# 6_shkb_upstream_con.net
KiCad netlist of a schematic drawn in Altium Designer
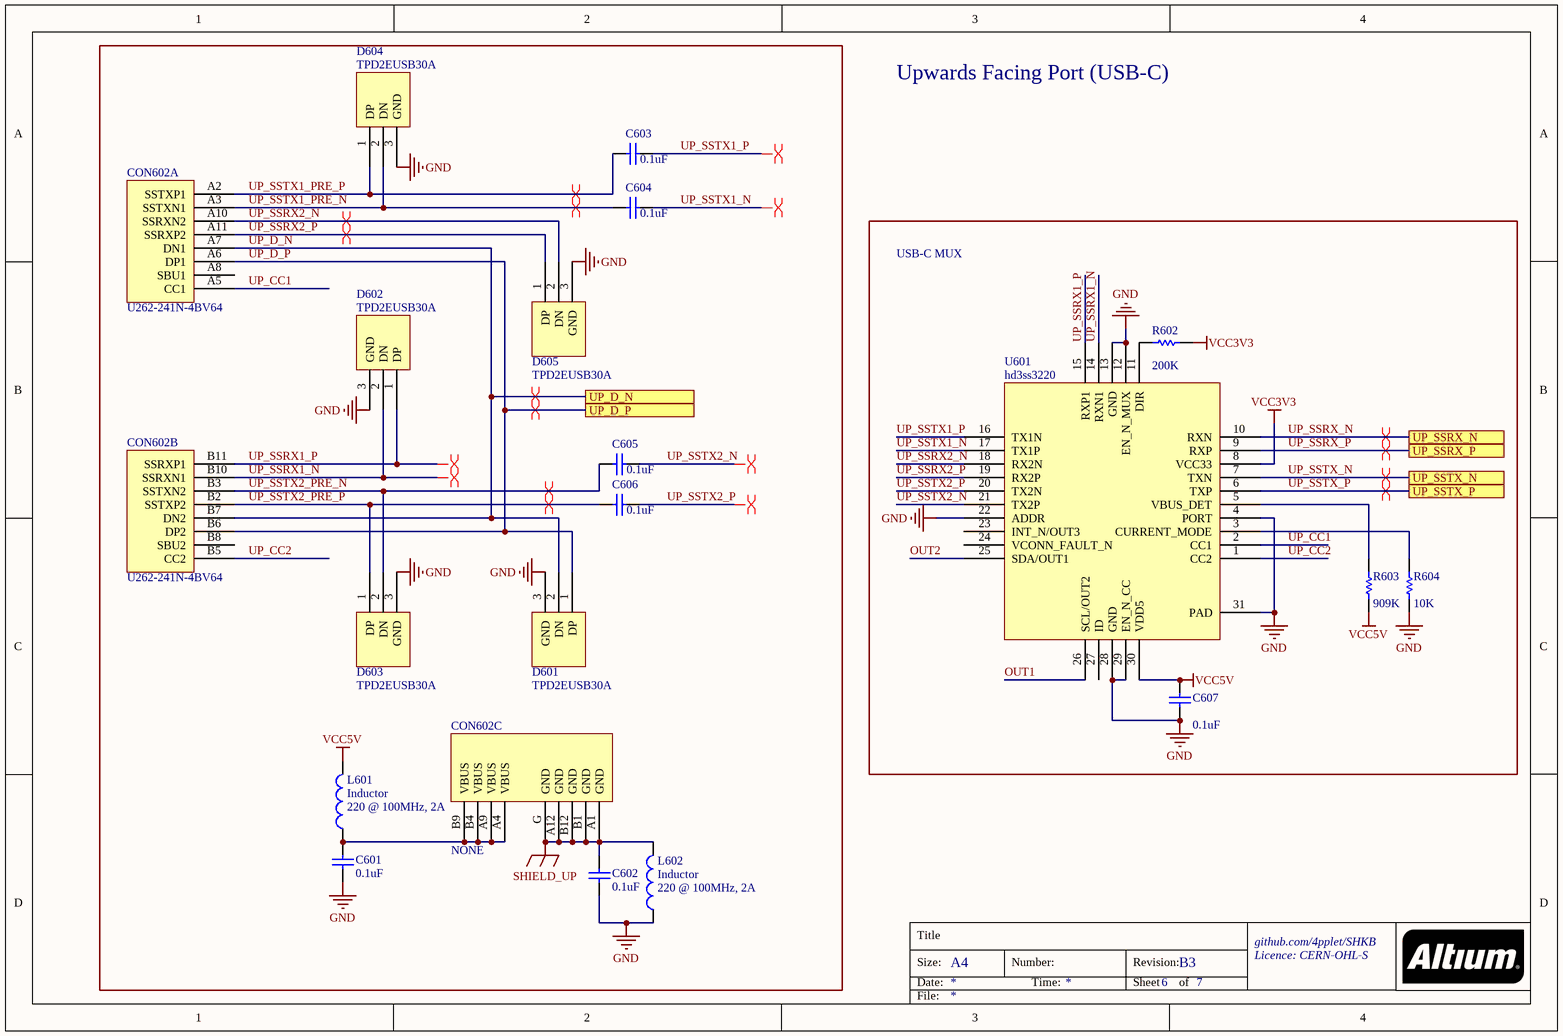
[diagram p0: 6_shkb_upstream_con.SchDoc]

(export (version "E")
  (design (tool "Eeschema 10.0.6"))
  (components
    (comp (ref "C601")
      (value "0.1uF")
      (footprint "C0603[1608]")
      (description "Capacitor")
      (fields (field (name "MFG") "KEMET") (field (name "LCSC PART #") "C14663"))
      (libsource (lib "Miscellaneous Devices") (part "Cap"))
    )
    (comp (ref "C602")
      (value "0.1uF")
      (footprint "C0603[1608]")
      (description "Capacitor")
      (fields (field (name "MFG") "KEMET") (field (name "LCSC PART #") "C14663"))
      (libsource (lib "Miscellaneous Devices") (part "Cap"))
    )
    (comp (ref "C603")
      (value "0.1uF")
      (footprint "C0402[1005]")
      (description "Capacitor")
      (fields (field (name "MFG") "KEMET") (field (name "LCSC PART #") "C1525"))
      (libsource (lib "Miscellaneous Devices") (part "Cap"))
    )
    (comp (ref "C604")
      (value "0.1uF")
      (footprint "C0402[1005]")
      (description "Capacitor")
      (fields (field (name "MFG") "KEMET") (field (name "LCSC PART #") "C1525"))
      (libsource (lib "Miscellaneous Devices") (part "Cap"))
    )
    (comp (ref "C605")
      (value "0.1uF")
      (footprint "C0402[1005]")
      (description "Capacitor")
      (fields (field (name "MFG") "KEMET") (field (name "LCSC PART #") "C1525"))
      (libsource (lib "Miscellaneous Devices") (part "Cap"))
    )
    (comp (ref "C606")
      (value "0.1uF")
      (footprint "C0402[1005]")
      (description "Capacitor")
      (fields (field (name "MFG") "KEMET") (field (name "LCSC PART #") "C1525"))
      (libsource (lib "Miscellaneous Devices") (part "Cap"))
    )
    (comp (ref "C607")
      (value "0.1uF")
      (footprint "C0603[1608]")
      (description "Capacitor")
      (fields (field (name "MFG") "KEMET") (field (name "LCSC PART #") "C14663"))
      (libsource (lib "Miscellaneous Devices") (part "Cap"))
    )
    (comp (ref "CON602")
      (value "for up to 1.6mm pcb")
      (footprint "XKB USB-C u262-241n-4bv64")
      (fields
        (field (name "JLC") "U262-241N-4BV64")
        (field (name "LCSC PART #") "C388660")
        (field (name "MRF.PART") "U262-241N-4BV64")
      )
      (libsource (lib "lib") (part "XKB USB-C u262-241n-4bv64"))
    )
    (comp (ref "D601")
      (value "TPD2EUSB30A")
      (footprint "TPD2EUSB30A")
      (fields
        (field (name "MFG") "Texas Instruments")
        (field (name "LCSC PART #") "C2844720")
        (field (name "MRF.PART") "TPD2EUSB30DRTR-TP")
      )
      (libsource (lib "") (part "TPD2EUSB30A_3"))
    )
    (comp (ref "D602")
      (value "TPD2EUSB30A")
      (footprint "TPD2EUSB30A")
      (fields
        (field (name "MFG") "Texas Instruments")
        (field (name "LCSC PART #") "C2844720")
        (field (name "MRF.PART") "TPD2EUSB30DRTR-TP")
      )
      (libsource (lib "lib") (part "TPD2EUSB30A"))
    )
    (comp (ref "D603")
      (value "TPD2EUSB30A")
      (footprint "TPD2EUSB30A")
      (fields
        (field (name "MFG") "Texas Instruments")
        (field (name "LCSC PART #") "C2844720")
        (field (name "MRF.PART") "TPD2EUSB30DRTR-TP")
      )
      (libsource (lib "") (part "TPD2EUSB30A_2"))
    )
    (comp (ref "D604")
      (value "TPD2EUSB30A")
      (footprint "TPD2EUSB30A")
      (fields
        (field (name "MFG") "Texas Instruments")
        (field (name "LCSC PART #") "C2844720")
        (field (name "MRF.PART") "TPD2EUSB30DRTR-TP")
      )
      (libsource (lib "") (part "TPD2EUSB30A_1"))
    )
    (comp (ref "D605")
      (value "TPD2EUSB30A")
      (footprint "TPD2EUSB30A")
      (fields
        (field (name "MFG") "Texas Instruments")
        (field (name "LCSC PART #") "C2844720")
        (field (name "MRF.PART") "TPD2EUSB30DRTR-TP")
      )
      (libsource (lib "") (part "TPD2EUSB30A_2"))
    )
    (comp (ref "L601")
      (value "Inductor")
      (footprint "L0603[1608]")
      (fields
        (field (name "ALTIUM_VALUE") "220 @ 100MHz, 2A")
        (field (name "MFG") "Murata Electronics North America")
        (field (name "LCSC PART #") "C85832")
        (field (name "MRF.PART") "BLM18KG331SN1D")
      )
      (libsource (lib "Miscellaneous Devices") (part "Inductor"))
    )
    (comp (ref "L602")
      (value "Inductor")
      (footprint "L0603[1608]")
      (fields
        (field (name "ALTIUM_VALUE") "220 @ 100MHz, 2A")
        (field (name "MFG") "Murata Electronics North America")
        (field (name "LCSC PART #") "C85832")
        (field (name "MRF.PART") "BLM18KG331SN1D")
      )
      (libsource (lib "Miscellaneous Devices") (part "Inductor"))
    )
    (comp (ref "R602")
      (value "200K")
      (footprint "R0603[1608]")
      (description "Resistor")
      (fields (field (name "MFG") "Vishay Dale") (field (name "LCSC PART #") "C25811"))
      (libsource (lib "Miscellaneous Devices") (part "Res1"))
    )
    (comp (ref "R603")
      (value "909K")
      (footprint "R0603[1608]")
      (description "Resistor")
      (fields (field (name "MFG") "Vishay Dale") (field (name "LCSC PART #") "C22935"))
      (libsource (lib "Miscellaneous Devices") (part "Res1"))
    )
    (comp (ref "R604")
      (value "10K")
      (footprint "R0603[1608]")
      (description "Resistor")
      (fields (field (name "MFG") "Vishay Dale") (field (name "LCSC PART #") "C25804"))
      (libsource (lib "Miscellaneous Devices") (part "Res1"))
    )
    (comp (ref "U601")
      (value "hd3ss3220")
      (footprint "hd3ss3220")
      (fields
        (field (name "MFG") "Texas Instruments")
        (field (name "LCSC PART #") "C165155")
        (field (name "MRF.PART") "HD3SS3220RNHR")
      )
      (libsource (lib "lib") (part "hd3ss3220"))
    )
  )
  (nets
    (net (code "1") (name "/OUT1") (class "Default")
      (node (ref "U601") (pin "26") (pinfunction "SCL/OUT2_26") (pintype "passive"))
    )
    (net (code "2") (name "/OUT2") (class "Default")
      (node (ref "U601") (pin "25") (pinfunction "SDA/OUT1_25") (pintype "passive"))
    )
    (net (code "3") (name "/UP_CC1") (class "Default")
      (node (ref "CON602") (pin "A5") (pinfunction "CC1_A5") (pintype "passive"))
      (node (ref "U601") (pin "2") (pinfunction "CC1_2") (pintype "passive"))
    )
    (net (code "4") (name "/UP_CC2") (class "Default")
      (node (ref "CON602") (pin "B5") (pinfunction "CC2_B5") (pintype "passive"))
      (node (ref "U601") (pin "1") (pinfunction "CC2_1") (pintype "passive"))
    )
    (net (code "5") (name "/UP_D_N") (class "Default")
      (node (ref "CON602") (pin "A7") (pinfunction "DN1_A7") (pintype "passive"))
      (node (ref "CON602") (pin "B7") (pinfunction "DN2_B7") (pintype "passive"))
      (node (ref "D601") (pin "2") (pinfunction "DN_2") (pintype "passive"))
    )
    (net (code "6") (name "/UP_D_P") (class "Default")
      (node (ref "CON602") (pin "A6") (pinfunction "DP1_A6") (pintype "passive"))
      (node (ref "CON602") (pin "B6") (pinfunction "DP2_B6") (pintype "passive"))
      (node (ref "D601") (pin "1") (pinfunction "DP_1") (pintype "passive"))
    )
    (net (code "7") (name "/UP_SSRX1_N") (class "Default")
      (node (ref "CON602") (pin "B10") (pinfunction "SSRXN1_B10") (pintype "passive"))
      (node (ref "D602") (pin "2") (pinfunction "DN_2") (pintype "passive"))
      (node (ref "U601") (pin "14") (pinfunction "RXN1_14") (pintype "passive"))
    )
    (net (code "8") (name "/UP_SSRX1_P") (class "Default")
      (node (ref "CON602") (pin "B11") (pinfunction "SSRXP1_B11") (pintype "passive"))
      (node (ref "D602") (pin "1") (pinfunction "DP_1") (pintype "passive"))
      (node (ref "U601") (pin "15") (pinfunction "RXP1_15") (pintype "passive"))
    )
    (net (code "9") (name "/UP_SSRX2_N") (class "Default")
      (node (ref "CON602") (pin "A10") (pinfunction "SSRXN2_A10") (pintype "passive"))
      (node (ref "D605") (pin "2") (pinfunction "DN_2") (pintype "passive"))
      (node (ref "U601") (pin "18") (pinfunction "RX2N_18") (pintype "passive"))
    )
    (net (code "10") (name "/UP_SSRX2_P") (class "Default")
      (node (ref "CON602") (pin "A11") (pinfunction "SSRXP2_A11") (pintype "passive"))
      (node (ref "D605") (pin "1") (pinfunction "DP_1") (pintype "passive"))
      (node (ref "U601") (pin "19") (pinfunction "RX2P_19") (pintype "passive"))
    )
    (net (code "11") (name "/UP_SSRX_N") (class "Default")
      (node (ref "U601") (pin "10") (pinfunction "RXN_10") (pintype "passive"))
    )
    (net (code "12") (name "/UP_SSRX_P") (class "Default")
      (node (ref "U601") (pin "9") (pinfunction "RXP_9") (pintype "passive"))
    )
    (net (code "13") (name "/UP_SSTX1_N") (class "Default")
      (node (ref "C604") (pin "2") (pinfunction "2_2") (pintype "passive"))
      (node (ref "U601") (pin "17") (pinfunction "TX1P_17") (pintype "passive"))
    )
    (net (code "14") (name "/UP_SSTX1_P") (class "Default")
      (node (ref "C603") (pin "2") (pinfunction "2_2") (pintype "passive"))
      (node (ref "U601") (pin "16") (pinfunction "TX1N_16") (pintype "passive"))
    )
    (net (code "15") (name "/UP_SSTX1_PRE_N") (class "Default")
      (node (ref "C604") (pin "1") (pinfunction "1_1") (pintype "passive"))
      (node (ref "CON602") (pin "A3") (pinfunction "SSTXN1_A3") (pintype "passive"))
      (node (ref "D604") (pin "2") (pinfunction "DN_2") (pintype "passive"))
    )
    (net (code "16") (name "/UP_SSTX1_PRE_P") (class "Default")
      (node (ref "C603") (pin "1") (pinfunction "1_1") (pintype "passive"))
      (node (ref "CON602") (pin "A2") (pinfunction "SSTXP1_A2") (pintype "passive"))
      (node (ref "D604") (pin "1") (pinfunction "DP_1") (pintype "passive"))
    )
    (net (code "17") (name "/UP_SSTX2_N") (class "Default")
      (node (ref "C605") (pin "2") (pinfunction "2_2") (pintype "passive"))
      (node (ref "U601") (pin "21") (pinfunction "TX2P_21") (pintype "passive"))
    )
    (net (code "18") (name "/UP_SSTX2_P") (class "Default")
      (node (ref "C606") (pin "2") (pinfunction "2_2") (pintype "passive"))
      (node (ref "U601") (pin "20") (pinfunction "TX2N_20") (pintype "passive"))
    )
    (net (code "19") (name "/UP_SSTX2_PRE_N") (class "Default")
      (node (ref "C605") (pin "1") (pinfunction "1_1") (pintype "passive"))
      (node (ref "CON602") (pin "B3") (pinfunction "SSTXN2_B3") (pintype "passive"))
      (node (ref "D603") (pin "2") (pinfunction "DN_2") (pintype "passive"))
    )
    (net (code "20") (name "/UP_SSTX2_PRE_P") (class "Default")
      (node (ref "C606") (pin "1") (pinfunction "1_1") (pintype "passive"))
      (node (ref "CON602") (pin "B2") (pinfunction "SSTXP2_B2") (pintype "passive"))
      (node (ref "D603") (pin "1") (pinfunction "DP_1") (pintype "passive"))
    )
    (net (code "21") (name "/UP_SSTX_N") (class "Default")
      (node (ref "U601") (pin "7") (pinfunction "TXN_7") (pintype "passive"))
    )
    (net (code "22") (name "/UP_SSTX_P") (class "Default")
      (node (ref "U601") (pin "6") (pinfunction "TXP_6") (pintype "passive"))
    )
    (net (code "23") (name "GND") (class "Default")
      (node (ref "C601") (pin "1") (pinfunction "1_1") (pintype "passive"))
      (node (ref "C602") (pin "1") (pinfunction "1_1") (pintype "passive"))
      (node (ref "C607") (pin "1") (pinfunction "1_1") (pintype "passive"))
      (node (ref "D601") (pin "3") (pinfunction "GND_3") (pintype "passive"))
      (node (ref "D602") (pin "3") (pinfunction "GND_3") (pintype "passive"))
      (node (ref "D603") (pin "3") (pinfunction "GND_3") (pintype "passive"))
      (node (ref "D604") (pin "3") (pinfunction "GND_3") (pintype "passive"))
      (node (ref "D605") (pin "3") (pinfunction "GND_3") (pintype "passive"))
      (node (ref "L602") (pin "1") (pinfunction "1_1") (pintype "passive"))
      (node (ref "R604") (pin "2") (pinfunction "2_2") (pintype "passive"))
      (node (ref "U601") (pin "12") (pinfunction "EN_N_MUX_12") (pintype "passive"))
      (node (ref "U601") (pin "13") (pinfunction "GND_13") (pintype "passive"))
      (node (ref "U601") (pin "22") (pinfunction "ADDR_22") (pintype "passive"))
      (node (ref "U601") (pin "28") (pinfunction "GND_28") (pintype "passive"))
      (node (ref "U601") (pin "29") (pinfunction "EN_N_CC_29") (pintype "passive"))
      (node (ref "U601") (pin "31") (pinfunction "PAD_31") (pintype "passive"))
      (node (ref "U601") (pin "4") (pinfunction "PORT_4") (pintype "passive"))
    )
    (net (code "24") (name "Net-(C601-Pad2)") (class "Default")
      (node (ref "C601") (pin "2") (pinfunction "2_2") (pintype "passive"))
      (node (ref "CON602") (pin "A4") (pinfunction "VBUS_A4") (pintype "passive"))
      (node (ref "CON602") (pin "A9") (pinfunction "VBUS_A9") (pintype "passive"))
      (node (ref "CON602") (pin "B4") (pinfunction "VBUS_B4") (pintype "passive"))
      (node (ref "CON602") (pin "B9") (pinfunction "VBUS_B9") (pintype "passive"))
      (node (ref "L601") (pin "1") (pinfunction "1_1") (pintype "passive"))
    )
    (net (code "25") (name "Net-(U601-CURRENT_MODE)") (class "Default")
      (node (ref "R604") (pin "1") (pinfunction "1_1") (pintype "passive"))
      (node (ref "U601") (pin "3") (pinfunction "CURRENT_MODE_3") (pintype "passive"))
    )
    (net (code "26") (name "Net-(U601-DIR)") (class "Default")
      (node (ref "R602") (pin "1") (pinfunction "1_1") (pintype "passive"))
      (node (ref "U601") (pin "11") (pinfunction "DIR_11") (pintype "passive"))
    )
    (net (code "27") (name "Net-(U601-VBUS_DET)") (class "Default")
      (node (ref "R603") (pin "1") (pinfunction "1_1") (pintype "passive"))
      (node (ref "U601") (pin "5") (pinfunction "VBUS_DET_5") (pintype "passive"))
    )
    (net (code "28") (name "SHIELD_UP") (class "Default")
      (node (ref "C602") (pin "2") (pinfunction "2_2") (pintype "passive"))
      (node (ref "CON602") (pin "A1") (pinfunction "GND_A1") (pintype "passive"))
      (node (ref "CON602") (pin "A12") (pinfunction "GND_A12") (pintype "passive"))
      (node (ref "CON602") (pin "B1") (pinfunction "GND_B1") (pintype "passive"))
      (node (ref "CON602") (pin "B12") (pinfunction "GND_B12") (pintype "passive"))
      (node (ref "CON602") (pin "G") (pinfunction "GND_G") (pintype "passive"))
      (node (ref "L602") (pin "2") (pinfunction "2_2") (pintype "passive"))
    )
    (net (code "29") (name "VCC3V3") (class "Default")
      (node (ref "R602") (pin "2") (pinfunction "2_2") (pintype "passive"))
      (node (ref "U601") (pin "8") (pinfunction "VCC33_8") (pintype "passive"))
    )
    (net (code "30") (name "VCC5V") (class "Default")
      (node (ref "C607") (pin "2") (pinfunction "2_2") (pintype "passive"))
      (node (ref "L601") (pin "2") (pinfunction "2_2") (pintype "passive"))
      (node (ref "R603") (pin "2") (pinfunction "2_2") (pintype "passive"))
      (node (ref "U601") (pin "30") (pinfunction "VDD5_30") (pintype "passive"))
    )
    (net (code "31") (name "unconnected-(CON602A-SBU1-PadA8)") (class "Default")
      (node (ref "CON602") (pin "A8") (pinfunction "SBU1_A8") (pintype "passive"))
    )
    (net (code "32") (name "unconnected-(CON602B-SBU2-PadB8)") (class "Default")
      (node (ref "CON602") (pin "B8") (pinfunction "SBU2_B8") (pintype "passive"))
    )
    (net (code "33") (name "unconnected-(U601-ID-Pad27)") (class "Default")
      (node (ref "U601") (pin "27") (pinfunction "ID_27") (pintype "passive"))
    )
    (net (code "34") (name "unconnected-(U601-INT_N{slash}OUT3-Pad23)") (class "Default")
      (node (ref "U601") (pin "23") (pinfunction "INT_N/OUT3_23") (pintype "passive"))
    )
    (net (code "35") (name "unconnected-(U601-VCONN_FAULT_N-Pad24)") (class "Default")
      (node (ref "U601") (pin "24") (pinfunction "VCONN_FAULT_N_24") (pintype "passive"))
    )
  )
)
